# TreeRocketometer.net
KiCad netlist of a schematic drawn in EAGLE
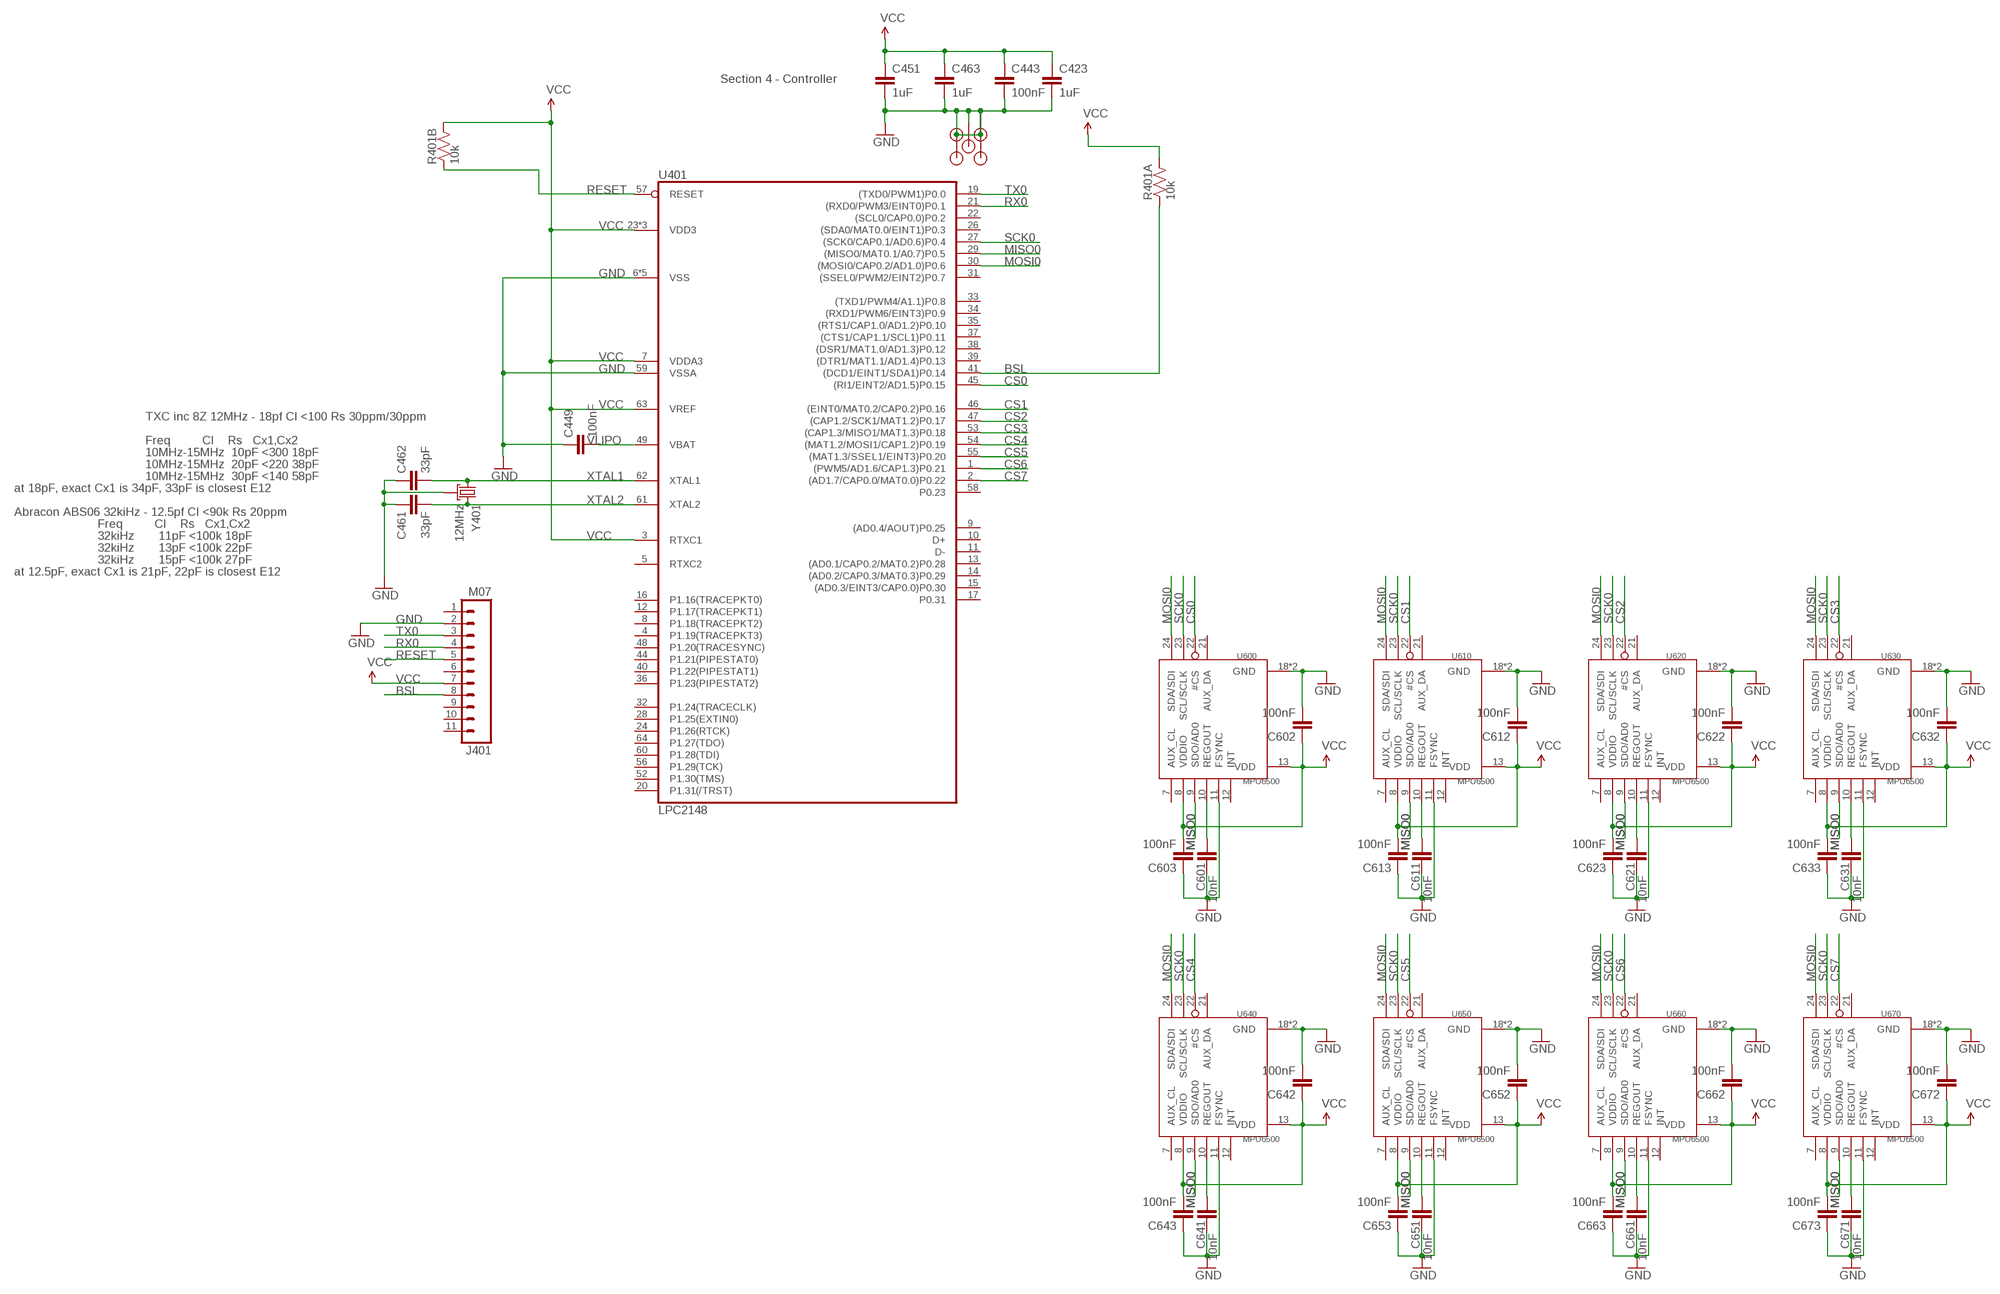
[diagram p0: schematic, sheet 1]

(export (version "E")
  (design (tool "Eeschema 10.0.6"))
  (components
    (comp (ref "C423")
      (value "1uF")
      (footprint "eagle-import:0402-CAP")
      (libsource (lib "eagle-import") (part "CAP0402-CAP"))
    )
    (comp (ref "C443")
      (value "100nF")
      (footprint "eagle-import:0402-CAP")
      (libsource (lib "eagle-import") (part "CAP0402-CAP"))
    )
    (comp (ref "C449")
      (value "100nF")
      (footprint "eagle-import:0402-CAP")
      (libsource (lib "eagle-import") (part "CAP0402-CAP"))
    )
    (comp (ref "C451")
      (value "1uF")
      (footprint "eagle-import:0402-CAP")
      (libsource (lib "eagle-import") (part "CAP0402-CAP"))
    )
    (comp (ref "C461")
      (value "33pF")
      (footprint "eagle-import:0402-CAP")
      (libsource (lib "eagle-import") (part "CAP0402-CAP"))
    )
    (comp (ref "C462")
      (value "33pF")
      (footprint "eagle-import:0402-CAP")
      (libsource (lib "eagle-import") (part "CAP0402-CAP"))
    )
    (comp (ref "C463")
      (value "1uF")
      (footprint "eagle-import:0402-CAP")
      (libsource (lib "eagle-import") (part "CAP0402-CAP"))
    )
    (comp (ref "C601")
      (value "10nF")
      (footprint "eagle-import:0402-CAP")
      (libsource (lib "eagle-import") (part "CAP0402-CAP"))
    )
    (comp (ref "C602")
      (value "100nF")
      (footprint "eagle-import:0402-CAP")
      (libsource (lib "eagle-import") (part "CAP0402-CAP"))
    )
    (comp (ref "C603")
      (value "100nF")
      (footprint "eagle-import:0402-CAP")
      (libsource (lib "eagle-import") (part "CAP0402-CAP"))
    )
    (comp (ref "C611")
      (value "10nF")
      (footprint "eagle-import:0402-CAP")
      (libsource (lib "eagle-import") (part "CAP0402-CAP"))
    )
    (comp (ref "C612")
      (value "100nF")
      (footprint "eagle-import:0402-CAP")
      (libsource (lib "eagle-import") (part "CAP0402-CAP"))
    )
    (comp (ref "C613")
      (value "100nF")
      (footprint "eagle-import:0402-CAP")
      (libsource (lib "eagle-import") (part "CAP0402-CAP"))
    )
    (comp (ref "C621")
      (value "10nF")
      (footprint "eagle-import:0402-CAP")
      (libsource (lib "eagle-import") (part "CAP0402-CAP"))
    )
    (comp (ref "C622")
      (value "100nF")
      (footprint "eagle-import:0402-CAP")
      (libsource (lib "eagle-import") (part "CAP0402-CAP"))
    )
    (comp (ref "C623")
      (value "100nF")
      (footprint "eagle-import:0402-CAP")
      (libsource (lib "eagle-import") (part "CAP0402-CAP"))
    )
    (comp (ref "C631")
      (value "10nF")
      (footprint "eagle-import:0402-CAP")
      (libsource (lib "eagle-import") (part "CAP0402-CAP"))
    )
    (comp (ref "C632")
      (value "100nF")
      (footprint "eagle-import:0402-CAP")
      (libsource (lib "eagle-import") (part "CAP0402-CAP"))
    )
    (comp (ref "C633")
      (value "100nF")
      (footprint "eagle-import:0402-CAP")
      (libsource (lib "eagle-import") (part "CAP0402-CAP"))
    )
    (comp (ref "C641")
      (value "10nF")
      (footprint "eagle-import:0402-CAP")
      (libsource (lib "eagle-import") (part "CAP0402-CAP"))
    )
    (comp (ref "C642")
      (value "100nF")
      (footprint "eagle-import:0402-CAP")
      (libsource (lib "eagle-import") (part "CAP0402-CAP"))
    )
    (comp (ref "C643")
      (value "100nF")
      (footprint "eagle-import:0402-CAP")
      (libsource (lib "eagle-import") (part "CAP0402-CAP"))
    )
    (comp (ref "C651")
      (value "10nF")
      (footprint "eagle-import:0402-CAP")
      (libsource (lib "eagle-import") (part "CAP0402-CAP"))
    )
    (comp (ref "C652")
      (value "100nF")
      (footprint "eagle-import:0402-CAP")
      (libsource (lib "eagle-import") (part "CAP0402-CAP"))
    )
    (comp (ref "C653")
      (value "100nF")
      (footprint "eagle-import:0402-CAP")
      (libsource (lib "eagle-import") (part "CAP0402-CAP"))
    )
    (comp (ref "C661")
      (value "10nF")
      (footprint "eagle-import:0402-CAP")
      (libsource (lib "eagle-import") (part "CAP0402-CAP"))
    )
    (comp (ref "C662")
      (value "100nF")
      (footprint "eagle-import:0402-CAP")
      (libsource (lib "eagle-import") (part "CAP0402-CAP"))
    )
    (comp (ref "C663")
      (value "100nF")
      (footprint "eagle-import:0402-CAP")
      (libsource (lib "eagle-import") (part "CAP0402-CAP"))
    )
    (comp (ref "C671")
      (value "10nF")
      (footprint "eagle-import:0402-CAP")
      (libsource (lib "eagle-import") (part "CAP0402-CAP"))
    )
    (comp (ref "C672")
      (value "100nF")
      (footprint "eagle-import:0402-CAP")
      (libsource (lib "eagle-import") (part "CAP0402-CAP"))
    )
    (comp (ref "C673")
      (value "100nF")
      (footprint "eagle-import:0402-CAP")
      (libsource (lib "eagle-import") (part "CAP0402-CAP"))
    )
    (comp (ref "J401")
      (value "M07")
      (footprint "eagle-import:1X11")
      (libsource (lib "eagle-import") (part "M11PTH"))
    )
    (comp (ref "JP1")
      (value "STANDOFF")
      (footprint "eagle-import:STANDOFF")
      (libsource (lib "eagle-import") (part "STANDOFF"))
    )
    (comp (ref "JP2")
      (value "STANDOFF")
      (footprint "eagle-import:STANDOFF")
      (libsource (lib "eagle-import") (part "STANDOFF"))
    )
    (comp (ref "JP3")
      (value "STANDOFF")
      (footprint "eagle-import:STANDOFF")
      (libsource (lib "eagle-import") (part "STANDOFF"))
    )
    (comp (ref "JP4")
      (value "STANDOFF")
      (footprint "eagle-import:STANDOFF")
      (libsource (lib "eagle-import") (part "STANDOFF"))
    )
    (comp (ref "JP5")
      (value "STANDOFF")
      (footprint "eagle-import:STANDOFF")
      (libsource (lib "eagle-import") (part "STANDOFF"))
    )
    (comp (ref "R401")
      (value "10k")
      (footprint "eagle-import:CRA04")
      (fields (field (name "DIGIKEY") "CRA4S810KCT-ND"))
      (libsource (lib "eagle-import") (part "RP404"))
    )
    (comp (ref "U401")
      (value "LPC2148")
      (footprint "eagle-import:LQFP64")
      (libsource (lib "eagle-import") (part "LPC2148"))
    )
    (comp (ref "U600")
      (value "MPU6500")
      (footprint "eagle-import:QFN24")
      (libsource (lib "eagle-import") (part "MPU6500"))
    )
    (comp (ref "U610")
      (value "MPU6500")
      (footprint "eagle-import:QFN24")
      (libsource (lib "eagle-import") (part "MPU6500"))
    )
    (comp (ref "U620")
      (value "MPU6500")
      (footprint "eagle-import:QFN24")
      (libsource (lib "eagle-import") (part "MPU6500"))
    )
    (comp (ref "U630")
      (value "MPU6500")
      (footprint "eagle-import:QFN24")
      (libsource (lib "eagle-import") (part "MPU6500"))
    )
    (comp (ref "U640")
      (value "MPU6500")
      (footprint "eagle-import:QFN24")
      (libsource (lib "eagle-import") (part "MPU6500"))
    )
    (comp (ref "U650")
      (value "MPU6500")
      (footprint "eagle-import:QFN24")
      (libsource (lib "eagle-import") (part "MPU6500"))
    )
    (comp (ref "U660")
      (value "MPU6500")
      (footprint "eagle-import:QFN24")
      (libsource (lib "eagle-import") (part "MPU6500"))
    )
    (comp (ref "U670")
      (value "MPU6500")
      (footprint "eagle-import:QFN24")
      (libsource (lib "eagle-import") (part "MPU6500"))
    )
    (comp (ref "Y401")
      (value "12MHz")
      (footprint "eagle-import:CRYSTAL_SMD_2MM_2_5MM")
      (libsource (lib "eagle-import") (part "CX2520"))
    )
  )
  (nets
    (net (code "1") (name "/BSL") (class "Default")
      (node (ref "J401") (pin "8") (pinfunction "8_8") (pintype "passive"))
      (node (ref "R401") (pin "1") (pinfunction "1_1") (pintype "passive"))
      (node (ref "U401") (pin "41") (pinfunction "(DCD1/EINT1/SDA1)P0.14_41") (pintype "bidirectional"))
    )
    (net (code "2") (name "/CS0") (class "Default")
      (node (ref "U401") (pin "45") (pinfunction "(RI1/EINT2/AD1.5)P0.15_45") (pintype "bidirectional"))
      (node (ref "U600") (pin "22") (pinfunction "#CS_22") (pintype "bidirectional"))
    )
    (net (code "3") (name "/CS1") (class "Default")
      (node (ref "U401") (pin "46") (pinfunction "(EINT0/MAT0.2/CAP0.2)P0.16_46") (pintype "bidirectional"))
      (node (ref "U610") (pin "22") (pinfunction "#CS_22") (pintype "bidirectional"))
    )
    (net (code "4") (name "/CS2") (class "Default")
      (node (ref "U401") (pin "47") (pinfunction "(CAP1.2/SCK1/MAT1.2)P0.17_47") (pintype "bidirectional"))
      (node (ref "U620") (pin "22") (pinfunction "#CS_22") (pintype "bidirectional"))
    )
    (net (code "5") (name "/CS3") (class "Default")
      (node (ref "U401") (pin "53") (pinfunction "(CAP1.3/MISO1/MAT1.3)P0.18_53") (pintype "bidirectional"))
      (node (ref "U630") (pin "22") (pinfunction "#CS_22") (pintype "bidirectional"))
    )
    (net (code "6") (name "/CS4") (class "Default")
      (node (ref "U401") (pin "54") (pinfunction "(MAT1.2/MOSI1/CAP1.2)P0.19_54") (pintype "bidirectional"))
      (node (ref "U640") (pin "22") (pinfunction "#CS_22") (pintype "bidirectional"))
    )
    (net (code "7") (name "/CS5") (class "Default")
      (node (ref "U401") (pin "55") (pinfunction "(MAT1.3/SSEL1/EINT3)P0.20_55") (pintype "bidirectional"))
      (node (ref "U650") (pin "22") (pinfunction "#CS_22") (pintype "bidirectional"))
    )
    (net (code "8") (name "/CS6") (class "Default")
      (node (ref "U401") (pin "1") (pinfunction "(PWM5/AD1.6/CAP1.3)P0.21_1") (pintype "bidirectional"))
      (node (ref "U660") (pin "22") (pinfunction "#CS_22") (pintype "bidirectional"))
    )
    (net (code "9") (name "/CS7") (class "Default")
      (node (ref "U401") (pin "2") (pinfunction "(AD1.7/CAP0.0/MAT0.0)P0.22_2") (pintype "bidirectional"))
      (node (ref "U670") (pin "22") (pinfunction "#CS_22") (pintype "bidirectional"))
    )
    (net (code "10") (name "/MISO0") (class "Default")
      (node (ref "U401") (pin "29") (pinfunction "(MISO0/MAT0.1/A0.7)P0.5_29") (pintype "bidirectional"))
      (node (ref "U600") (pin "9") (pinfunction "SDO/AD0_9") (pintype "output"))
      (node (ref "U610") (pin "9") (pinfunction "SDO/AD0_9") (pintype "output"))
      (node (ref "U620") (pin "9") (pinfunction "SDO/AD0_9") (pintype "output"))
      (node (ref "U630") (pin "9") (pinfunction "SDO/AD0_9") (pintype "output"))
      (node (ref "U640") (pin "9") (pinfunction "SDO/AD0_9") (pintype "output"))
      (node (ref "U650") (pin "9") (pinfunction "SDO/AD0_9") (pintype "output"))
      (node (ref "U660") (pin "9") (pinfunction "SDO/AD0_9") (pintype "output"))
      (node (ref "U670") (pin "9") (pinfunction "SDO/AD0_9") (pintype "output"))
    )
    (net (code "11") (name "/MOSI0") (class "Default")
      (node (ref "U401") (pin "30") (pinfunction "(MOSI0/CAP0.2/AD1.0)P0.6_30") (pintype "bidirectional"))
      (node (ref "U600") (pin "24") (pinfunction "SDA/SDI_24") (pintype "bidirectional"))
      (node (ref "U610") (pin "24") (pinfunction "SDA/SDI_24") (pintype "bidirectional"))
      (node (ref "U620") (pin "24") (pinfunction "SDA/SDI_24") (pintype "bidirectional"))
      (node (ref "U630") (pin "24") (pinfunction "SDA/SDI_24") (pintype "bidirectional"))
      (node (ref "U640") (pin "24") (pinfunction "SDA/SDI_24") (pintype "bidirectional"))
      (node (ref "U650") (pin "24") (pinfunction "SDA/SDI_24") (pintype "bidirectional"))
      (node (ref "U660") (pin "24") (pinfunction "SDA/SDI_24") (pintype "bidirectional"))
      (node (ref "U670") (pin "24") (pinfunction "SDA/SDI_24") (pintype "bidirectional"))
    )
    (net (code "12") (name "/RESET") (class "Default")
      (node (ref "J401") (pin "5") (pinfunction "5_5") (pintype "passive"))
      (node (ref "R401") (pin "2") (pinfunction "1_2") (pintype "passive"))
      (node (ref "U401") (pin "57") (pinfunction "RESET_57") (pintype "input"))
    )
    (net (code "13") (name "/RX0") (class "Default")
      (node (ref "J401") (pin "4") (pinfunction "4_4") (pintype "passive"))
      (node (ref "U401") (pin "21") (pinfunction "(RXD0/PWM3/EINT0)P0.1_21") (pintype "bidirectional"))
    )
    (net (code "14") (name "/SCK0") (class "Default")
      (node (ref "U401") (pin "27") (pinfunction "(SCK0/CAP0.1/AD0.6)P0.4_27") (pintype "bidirectional"))
      (node (ref "U600") (pin "23") (pinfunction "SCL/SCLK_23") (pintype "bidirectional"))
      (node (ref "U610") (pin "23") (pinfunction "SCL/SCLK_23") (pintype "bidirectional"))
      (node (ref "U620") (pin "23") (pinfunction "SCL/SCLK_23") (pintype "bidirectional"))
      (node (ref "U630") (pin "23") (pinfunction "SCL/SCLK_23") (pintype "bidirectional"))
      (node (ref "U640") (pin "23") (pinfunction "SCL/SCLK_23") (pintype "bidirectional"))
      (node (ref "U650") (pin "23") (pinfunction "SCL/SCLK_23") (pintype "bidirectional"))
      (node (ref "U660") (pin "23") (pinfunction "SCL/SCLK_23") (pintype "bidirectional"))
      (node (ref "U670") (pin "23") (pinfunction "SCL/SCLK_23") (pintype "bidirectional"))
    )
    (net (code "15") (name "/TX0") (class "Default")
      (node (ref "J401") (pin "3") (pinfunction "3_3") (pintype "passive"))
      (node (ref "U401") (pin "19") (pinfunction "(TXD0/PWM1)P0.0_19") (pintype "bidirectional"))
    )
    (net (code "16") (name "/VLIPO") (class "Default")
      (node (ref "C449") (pin "2") (pinfunction "2_2") (pintype "passive"))
      (node (ref "U401") (pin "49") (pinfunction "VBAT_49") (pintype "power_in"))
    )
    (net (code "17") (name "/XTAL1") (class "Default")
      (node (ref "C462") (pin "2") (pinfunction "2_2") (pintype "passive"))
      (node (ref "U401") (pin "62") (pinfunction "XTAL1_62") (pintype "input"))
      (node (ref "Y401") (pin "1") (pinfunction "1_1") (pintype "passive"))
    )
    (net (code "18") (name "/XTAL2") (class "Default")
      (node (ref "C461") (pin "2") (pinfunction "2_2") (pintype "passive"))
      (node (ref "U401") (pin "61") (pinfunction "XTAL2_61") (pintype "output"))
      (node (ref "Y401") (pin "3") (pinfunction "2_3") (pintype "passive"))
    )
    (net (code "19") (name "GND") (class "Default")
      (node (ref "C423") (pin "2") (pinfunction "2_2") (pintype "passive"))
      (node (ref "C443") (pin "2") (pinfunction "2_2") (pintype "passive"))
      (node (ref "C449") (pin "1") (pinfunction "1_1") (pintype "passive"))
      (node (ref "C451") (pin "2") (pinfunction "2_2") (pintype "passive"))
      (node (ref "C461") (pin "1") (pinfunction "1_1") (pintype "passive"))
      (node (ref "C462") (pin "1") (pinfunction "1_1") (pintype "passive"))
      (node (ref "C463") (pin "2") (pinfunction "2_2") (pintype "passive"))
      (node (ref "C601") (pin "2") (pinfunction "2_2") (pintype "passive"))
      (node (ref "C602") (pin "2") (pinfunction "2_2") (pintype "passive"))
      (node (ref "C603") (pin "1") (pinfunction "1_1") (pintype "passive"))
      (node (ref "C611") (pin "2") (pinfunction "2_2") (pintype "passive"))
      (node (ref "C612") (pin "2") (pinfunction "2_2") (pintype "passive"))
      (node (ref "C613") (pin "1") (pinfunction "1_1") (pintype "passive"))
      (node (ref "C621") (pin "2") (pinfunction "2_2") (pintype "passive"))
      (node (ref "C622") (pin "2") (pinfunction "2_2") (pintype "passive"))
      (node (ref "C623") (pin "1") (pinfunction "1_1") (pintype "passive"))
      (node (ref "C631") (pin "2") (pinfunction "2_2") (pintype "passive"))
      (node (ref "C632") (pin "2") (pinfunction "2_2") (pintype "passive"))
      (node (ref "C633") (pin "1") (pinfunction "1_1") (pintype "passive"))
      (node (ref "C641") (pin "2") (pinfunction "2_2") (pintype "passive"))
      (node (ref "C642") (pin "2") (pinfunction "2_2") (pintype "passive"))
      (node (ref "C643") (pin "1") (pinfunction "1_1") (pintype "passive"))
      (node (ref "C651") (pin "2") (pinfunction "2_2") (pintype "passive"))
      (node (ref "C652") (pin "2") (pinfunction "2_2") (pintype "passive"))
      (node (ref "C653") (pin "1") (pinfunction "1_1") (pintype "passive"))
      (node (ref "C661") (pin "2") (pinfunction "2_2") (pintype "passive"))
      (node (ref "C662") (pin "2") (pinfunction "2_2") (pintype "passive"))
      (node (ref "C663") (pin "1") (pinfunction "1_1") (pintype "passive"))
      (node (ref "C671") (pin "2") (pinfunction "2_2") (pintype "passive"))
      (node (ref "C672") (pin "2") (pinfunction "2_2") (pintype "passive"))
      (node (ref "C673") (pin "1") (pinfunction "1_1") (pintype "passive"))
      (node (ref "J401") (pin "2") (pinfunction "2_2") (pintype "passive"))
      (node (ref "JP1") (pin "P$1") (pinfunction "P$1_P$1") (pintype "bidirectional"))
      (node (ref "JP2") (pin "P$1") (pinfunction "P$1_P$1") (pintype "bidirectional"))
      (node (ref "JP3") (pin "P$1") (pinfunction "P$1_P$1") (pintype "bidirectional"))
      (node (ref "JP4") (pin "P$1") (pinfunction "P$1_P$1") (pintype "bidirectional"))
      (node (ref "JP5") (pin "P$1") (pinfunction "P$1_P$1") (pintype "bidirectional"))
      (node (ref "U401") (pin "18") (pinfunction "VSS_18") (pintype "power_in"))
      (node (ref "U401") (pin "25") (pinfunction "VSS_25") (pintype "power_in"))
      (node (ref "U401") (pin "42") (pinfunction "VSS_42") (pintype "power_in"))
      (node (ref "U401") (pin "50") (pinfunction "VSS_50") (pintype "power_in"))
      (node (ref "U401") (pin "59") (pinfunction "VSSA_59") (pintype "power_in"))
      (node (ref "U401") (pin "6") (pinfunction "VSS_6") (pintype "power_in"))
      (node (ref "U600") (pin "11") (pinfunction "FSYNC_11") (pintype "bidirectional"))
      (node (ref "U600") (pin "18") (pinfunction "GND_18") (pintype "power_in"))
      (node (ref "U600") (pin "20") (pinfunction "GND_20") (pintype "power_in"))
      (node (ref "U610") (pin "11") (pinfunction "FSYNC_11") (pintype "bidirectional"))
      (node (ref "U610") (pin "18") (pinfunction "GND_18") (pintype "power_in"))
      (node (ref "U610") (pin "20") (pinfunction "GND_20") (pintype "power_in"))
      (node (ref "U620") (pin "11") (pinfunction "FSYNC_11") (pintype "bidirectional"))
      (node (ref "U620") (pin "18") (pinfunction "GND_18") (pintype "power_in"))
      (node (ref "U620") (pin "20") (pinfunction "GND_20") (pintype "power_in"))
      (node (ref "U630") (pin "11") (pinfunction "FSYNC_11") (pintype "bidirectional"))
      (node (ref "U630") (pin "18") (pinfunction "GND_18") (pintype "power_in"))
      (node (ref "U630") (pin "20") (pinfunction "GND_20") (pintype "power_in"))
      (node (ref "U640") (pin "11") (pinfunction "FSYNC_11") (pintype "bidirectional"))
      (node (ref "U640") (pin "18") (pinfunction "GND_18") (pintype "power_in"))
      (node (ref "U640") (pin "20") (pinfunction "GND_20") (pintype "power_in"))
      (node (ref "U650") (pin "11") (pinfunction "FSYNC_11") (pintype "bidirectional"))
      (node (ref "U650") (pin "18") (pinfunction "GND_18") (pintype "power_in"))
      (node (ref "U650") (pin "20") (pinfunction "GND_20") (pintype "power_in"))
      (node (ref "U660") (pin "11") (pinfunction "FSYNC_11") (pintype "bidirectional"))
      (node (ref "U660") (pin "18") (pinfunction "GND_18") (pintype "power_in"))
      (node (ref "U660") (pin "20") (pinfunction "GND_20") (pintype "power_in"))
      (node (ref "U670") (pin "11") (pinfunction "FSYNC_11") (pintype "bidirectional"))
      (node (ref "U670") (pin "18") (pinfunction "GND_18") (pintype "power_in"))
      (node (ref "U670") (pin "20") (pinfunction "GND_20") (pintype "power_in"))
      (node (ref "Y401") (pin "2") (pinfunction "GND_2") (pintype "passive"))
      (node (ref "Y401") (pin "4") (pinfunction "GND_4") (pintype "passive"))
    )
    (net (code "20") (name "Net-(U600-REGOUT)") (class "Default")
      (node (ref "C601") (pin "1") (pinfunction "1_1") (pintype "passive"))
      (node (ref "U600") (pin "10") (pinfunction "REGOUT_10") (pintype "bidirectional"))
    )
    (net (code "21") (name "Net-(U610-REGOUT)") (class "Default")
      (node (ref "C611") (pin "1") (pinfunction "1_1") (pintype "passive"))
      (node (ref "U610") (pin "10") (pinfunction "REGOUT_10") (pintype "bidirectional"))
    )
    (net (code "22") (name "Net-(U620-REGOUT)") (class "Default")
      (node (ref "C621") (pin "1") (pinfunction "1_1") (pintype "passive"))
      (node (ref "U620") (pin "10") (pinfunction "REGOUT_10") (pintype "bidirectional"))
    )
    (net (code "23") (name "Net-(U630-REGOUT)") (class "Default")
      (node (ref "C631") (pin "1") (pinfunction "1_1") (pintype "passive"))
      (node (ref "U630") (pin "10") (pinfunction "REGOUT_10") (pintype "bidirectional"))
    )
    (net (code "24") (name "Net-(U640-REGOUT)") (class "Default")
      (node (ref "C641") (pin "1") (pinfunction "1_1") (pintype "passive"))
      (node (ref "U640") (pin "10") (pinfunction "REGOUT_10") (pintype "bidirectional"))
    )
    (net (code "25") (name "Net-(U650-REGOUT)") (class "Default")
      (node (ref "C651") (pin "1") (pinfunction "1_1") (pintype "passive"))
      (node (ref "U650") (pin "10") (pinfunction "REGOUT_10") (pintype "bidirectional"))
    )
    (net (code "26") (name "Net-(U660-REGOUT)") (class "Default")
      (node (ref "C661") (pin "1") (pinfunction "1_1") (pintype "passive"))
      (node (ref "U660") (pin "10") (pinfunction "REGOUT_10") (pintype "bidirectional"))
    )
    (net (code "27") (name "Net-(U670-REGOUT)") (class "Default")
      (node (ref "C671") (pin "1") (pinfunction "1_1") (pintype "passive"))
      (node (ref "U670") (pin "10") (pinfunction "REGOUT_10") (pintype "bidirectional"))
    )
    (net (code "28") (name "VCC") (class "Default")
      (node (ref "C423") (pin "1") (pinfunction "1_1") (pintype "passive"))
      (node (ref "C443") (pin "1") (pinfunction "1_1") (pintype "passive"))
      (node (ref "C451") (pin "1") (pinfunction "1_1") (pintype "passive"))
      (node (ref "C463") (pin "1") (pinfunction "1_1") (pintype "passive"))
      (node (ref "C602") (pin "1") (pinfunction "1_1") (pintype "passive"))
      (node (ref "C603") (pin "2") (pinfunction "2_2") (pintype "passive"))
      (node (ref "C612") (pin "1") (pinfunction "1_1") (pintype "passive"))
      (node (ref "C613") (pin "2") (pinfunction "2_2") (pintype "passive"))
      (node (ref "C622") (pin "1") (pinfunction "1_1") (pintype "passive"))
      (node (ref "C623") (pin "2") (pinfunction "2_2") (pintype "passive"))
      (node (ref "C632") (pin "1") (pinfunction "1_1") (pintype "passive"))
      (node (ref "C633") (pin "2") (pinfunction "2_2") (pintype "passive"))
      (node (ref "C642") (pin "1") (pinfunction "1_1") (pintype "passive"))
      (node (ref "C643") (pin "2") (pinfunction "2_2") (pintype "passive"))
      (node (ref "C652") (pin "1") (pinfunction "1_1") (pintype "passive"))
      (node (ref "C653") (pin "2") (pinfunction "2_2") (pintype "passive"))
      (node (ref "C662") (pin "1") (pinfunction "1_1") (pintype "passive"))
      (node (ref "C663") (pin "2") (pinfunction "2_2") (pintype "passive"))
      (node (ref "C672") (pin "1") (pinfunction "1_1") (pintype "passive"))
      (node (ref "C673") (pin "2") (pinfunction "2_2") (pintype "passive"))
      (node (ref "J401") (pin "7") (pinfunction "7_7") (pintype "passive"))
      (node (ref "R401") (pin "7") (pinfunction "2_7") (pintype "passive"))
      (node (ref "R401") (pin "8") (pinfunction "2_8") (pintype "passive"))
      (node (ref "U401") (pin "23") (pinfunction "VDD3_23") (pintype "power_in"))
      (node (ref "U401") (pin "3") (pinfunction "RTXC1_3") (pintype "input"))
      (node (ref "U401") (pin "43") (pinfunction "VDD3_43") (pintype "power_in"))
      (node (ref "U401") (pin "51") (pinfunction "VDD3_51") (pintype "power_in"))
      (node (ref "U401") (pin "63") (pinfunction "VREF_63") (pintype "input"))
      (node (ref "U401") (pin "7") (pinfunction "VDDA3_7") (pintype "power_in"))
      (node (ref "U600") (pin "13") (pinfunction "VDD_13") (pintype "power_in"))
      (node (ref "U600") (pin "8") (pinfunction "VDDIO_8") (pintype "bidirectional"))
      (node (ref "U610") (pin "13") (pinfunction "VDD_13") (pintype "power_in"))
      (node (ref "U610") (pin "8") (pinfunction "VDDIO_8") (pintype "bidirectional"))
      (node (ref "U620") (pin "13") (pinfunction "VDD_13") (pintype "power_in"))
      (node (ref "U620") (pin "8") (pinfunction "VDDIO_8") (pintype "bidirectional"))
      (node (ref "U630") (pin "13") (pinfunction "VDD_13") (pintype "power_in"))
      (node (ref "U630") (pin "8") (pinfunction "VDDIO_8") (pintype "bidirectional"))
      (node (ref "U640") (pin "13") (pinfunction "VDD_13") (pintype "power_in"))
      (node (ref "U640") (pin "8") (pinfunction "VDDIO_8") (pintype "bidirectional"))
      (node (ref "U650") (pin "13") (pinfunction "VDD_13") (pintype "power_in"))
      (node (ref "U650") (pin "8") (pinfunction "VDDIO_8") (pintype "bidirectional"))
      (node (ref "U660") (pin "13") (pinfunction "VDD_13") (pintype "power_in"))
      (node (ref "U660") (pin "8") (pinfunction "VDDIO_8") (pintype "bidirectional"))
      (node (ref "U670") (pin "13") (pinfunction "VDD_13") (pintype "power_in"))
      (node (ref "U670") (pin "8") (pinfunction "VDDIO_8") (pintype "bidirectional"))
    )
    (net (code "29") (name "unconnected-(J401-Pad1)") (class "Default")
      (node (ref "J401") (pin "1") (pinfunction "1_1") (pintype "passive"))
    )
    (net (code "30") (name "unconnected-(J401-Pad6)") (class "Default")
      (node (ref "J401") (pin "6") (pinfunction "6_6") (pintype "passive"))
    )
    (net (code "31") (name "unconnected-(J401-Pad9)") (class "Default")
      (node (ref "J401") (pin "9") (pinfunction "9_9") (pintype "passive"))
    )
    (net (code "32") (name "unconnected-(J401-Pad10)") (class "Default")
      (node (ref "J401") (pin "10") (pinfunction "10_10") (pintype "passive"))
    )
    (net (code "33") (name "unconnected-(J401-Pad11)") (class "Default")
      (node (ref "J401") (pin "11") (pinfunction "11_11") (pintype "passive"))
    )
    (net (code "34") (name "unconnected-(U401-(AD0.1{slash}CAP0.2{slash}MAT0.2)P0.28-Pad13)") (class "Default")
      (node (ref "U401") (pin "13") (pinfunction "(AD0.1/CAP0.2/MAT0.2)P0.28_13") (pintype "bidirectional"))
    )
    (net (code "35") (name "unconnected-(U401-(AD0.2{slash}CAP0.3{slash}MAT0.3)P0.29-Pad14)") (class "Default")
      (node (ref "U401") (pin "14") (pinfunction "(AD0.2/CAP0.3/MAT0.3)P0.29_14") (pintype "bidirectional"))
    )
    (net (code "36") (name "unconnected-(U401-(AD0.3{slash}EINT3{slash}CAP0.0)P0.30-Pad15)") (class "Default")
      (node (ref "U401") (pin "15") (pinfunction "(AD0.3/EINT3/CAP0.0)P0.30_15") (pintype "bidirectional"))
    )
    (net (code "37") (name "unconnected-(U401-(AD0.4{slash}AOUT)P0.25-Pad9)") (class "Default")
      (node (ref "U401") (pin "9") (pinfunction "(AD0.4/AOUT)P0.25_9") (pintype "bidirectional"))
    )
    (net (code "38") (name "unconnected-(U401-(CTS1{slash}CAP1.1{slash}SCL1)P0.11-Pad37)") (class "Default")
      (node (ref "U401") (pin "37") (pinfunction "(CTS1/CAP1.1/SCL1)P0.11_37") (pintype "bidirectional"))
    )
    (net (code "39") (name "unconnected-(U401-(DSR1{slash}MAT1.0{slash}AD1.3)P0.12-Pad38)") (class "Default")
      (node (ref "U401") (pin "38") (pinfunction "(DSR1/MAT1.0/AD1.3)P0.12_38") (pintype "bidirectional"))
    )
    (net (code "40") (name "unconnected-(U401-(DTR1{slash}MAT1.1{slash}AD1.4)P0.13-Pad39)") (class "Default")
      (node (ref "U401") (pin "39") (pinfunction "(DTR1/MAT1.1/AD1.4)P0.13_39") (pintype "bidirectional"))
    )
    (net (code "41") (name "unconnected-(U401-(RTS1{slash}CAP1.0{slash}AD1.2)P0.10-Pad35)") (class "Default")
      (node (ref "U401") (pin "35") (pinfunction "(RTS1/CAP1.0/AD1.2)P0.10_35") (pintype "bidirectional"))
    )
    (net (code "42") (name "unconnected-(U401-(RXD1{slash}PWM6{slash}EINT3)P0.9-Pad34)") (class "Default")
      (node (ref "U401") (pin "34") (pinfunction "(RXD1/PWM6/EINT3)P0.9_34") (pintype "bidirectional"))
    )
    (net (code "43") (name "unconnected-(U401-(SCL0{slash}CAP0.0)P0.2-Pad22)") (class "Default")
      (node (ref "U401") (pin "22") (pinfunction "(SCL0/CAP0.0)P0.2_22") (pintype "bidirectional"))
    )
    (net (code "44") (name "unconnected-(U401-(SDA0{slash}MAT0.0{slash}EINT1)P0.3-Pad26)") (class "Default")
      (node (ref "U401") (pin "26") (pinfunction "(SDA0/MAT0.0/EINT1)P0.3_26") (pintype "bidirectional"))
    )
    (net (code "45") (name "unconnected-(U401-(SSEL0{slash}PWM2{slash}EINT2)P0.7-Pad31)") (class "Default")
      (node (ref "U401") (pin "31") (pinfunction "(SSEL0/PWM2/EINT2)P0.7_31") (pintype "bidirectional"))
    )
    (net (code "46") (name "unconnected-(U401-(TXD1{slash}PWM4{slash}A1.1)P0.8-Pad33)") (class "Default")
      (node (ref "U401") (pin "33") (pinfunction "(TXD1/PWM4/A1.1)P0.8_33") (pintype "bidirectional"))
    )
    (net (code "47") (name "unconnected-(U401-D+-Pad10)") (class "Default")
      (node (ref "U401") (pin "10") (pinfunction "D+_10") (pintype "bidirectional"))
    )
    (net (code "48") (name "unconnected-(U401-D--Pad11)") (class "Default")
      (node (ref "U401") (pin "11") (pinfunction "D-_11") (pintype "bidirectional"))
    )
    (net (code "49") (name "unconnected-(U401-P0.23-Pad58)") (class "Default")
      (node (ref "U401") (pin "58") (pinfunction "P0.23_58") (pintype "bidirectional"))
    )
    (net (code "50") (name "unconnected-(U401-P0.31-Pad17)") (class "Default")
      (node (ref "U401") (pin "17") (pinfunction "P0.31_17") (pintype "output"))
    )
    (net (code "51") (name "unconnected-(U401-P1.16(TRACEPKT0)-Pad16)") (class "Default")
      (node (ref "U401") (pin "16") (pinfunction "P1.16(TRACEPKT0)_16") (pintype "bidirectional"))
    )
    (net (code "52") (name "unconnected-(U401-P1.17(TRACEPKT1)-Pad12)") (class "Default")
      (node (ref "U401") (pin "12") (pinfunction "P1.17(TRACEPKT1)_12") (pintype "bidirectional"))
    )
    (net (code "53") (name "unconnected-(U401-P1.18(TRACEPKT2)-Pad8)") (class "Default")
      (node (ref "U401") (pin "8") (pinfunction "P1.18(TRACEPKT2)_8") (pintype "bidirectional"))
    )
    (net (code "54") (name "unconnected-(U401-P1.19(TRACEPKT3)-Pad4)") (class "Default")
      (node (ref "U401") (pin "4") (pinfunction "P1.19(TRACEPKT3)_4") (pintype "bidirectional"))
    )
    (net (code "55") (name "unconnected-(U401-P1.20(TRACESYNC)-Pad48)") (class "Default")
      (node (ref "U401") (pin "48") (pinfunction "P1.20(TRACESYNC)_48") (pintype "bidirectional"))
    )
    (net (code "56") (name "unconnected-(U401-P1.21(PIPESTAT0)-Pad44)") (class "Default")
      (node (ref "U401") (pin "44") (pinfunction "P1.21(PIPESTAT0)_44") (pintype "bidirectional"))
    )
    (net (code "57") (name "unconnected-(U401-P1.22(PIPESTAT1)-Pad40)") (class "Default")
      (node (ref "U401") (pin "40") (pinfunction "P1.22(PIPESTAT1)_40") (pintype "bidirectional"))
    )
    (net (code "58") (name "unconnected-(U401-P1.23(PIPESTAT2)-Pad36)") (class "Default")
      (node (ref "U401") (pin "36") (pinfunction "P1.23(PIPESTAT2)_36") (pintype "bidirectional"))
    )
    (net (code "59") (name "unconnected-(U401-P1.24(TRACECLK)-Pad32)") (class "Default")
      (node (ref "U401") (pin "32") (pinfunction "P1.24(TRACECLK)_32") (pintype "bidirectional"))
    )
    (net (code "60") (name "unconnected-(U401-P1.25(EXTIN0)-Pad28)") (class "Default")
      (node (ref "U401") (pin "28") (pinfunction "P1.25(EXTIN0)_28") (pintype "bidirectional"))
    )
    (net (code "61") (name "unconnected-(U401-P1.26(RTCK)-Pad24)") (class "Default")
      (node (ref "U401") (pin "24") (pinfunction "P1.26(RTCK)_24") (pintype "bidirectional"))
    )
    (net (code "62") (name "unconnected-(U401-P1.27(TDO)-Pad64)") (class "Default")
      (node (ref "U401") (pin "64") (pinfunction "P1.27(TDO)_64") (pintype "bidirectional"))
    )
    (net (code "63") (name "unconnected-(U401-P1.28(TDI)-Pad60)") (class "Default")
      (node (ref "U401") (pin "60") (pinfunction "P1.28(TDI)_60") (pintype "bidirectional"))
    )
    (net (code "64") (name "unconnected-(U401-P1.29(TCK)-Pad56)") (class "Default")
      (node (ref "U401") (pin "56") (pinfunction "P1.29(TCK)_56") (pintype "bidirectional"))
    )
    (net (code "65") (name "unconnected-(U401-P1.30(TMS)-Pad52)") (class "Default")
      (node (ref "U401") (pin "52") (pinfunction "P1.30(TMS)_52") (pintype "bidirectional"))
    )
    (net (code "66") (name "unconnected-(U401-P1.31({slash}TRST)-Pad20)") (class "Default")
      (node (ref "U401") (pin "20") (pinfunction "P1.31(/TRST)_20") (pintype "bidirectional"))
    )
    (net (code "67") (name "unconnected-(U401-RTXC2-Pad5)") (class "Default")
      (node (ref "U401") (pin "5") (pinfunction "RTXC2_5") (pintype "output"))
    )
    (net (code "68") (name "unconnected-(U600-AUX_CL-Pad7)") (class "Default")
      (node (ref "U600") (pin "7") (pinfunction "AUX_CL_7") (pintype "bidirectional"))
    )
    (net (code "69") (name "unconnected-(U600-AUX_DA-Pad21)") (class "Default")
      (node (ref "U600") (pin "21") (pinfunction "AUX_DA_21") (pintype "bidirectional"))
    )
    (net (code "70") (name "unconnected-(U600-INT-Pad12)") (class "Default")
      (node (ref "U600") (pin "12") (pinfunction "INT_12") (pintype "output"))
    )
    (net (code "71") (name "unconnected-(U610-AUX_CL-Pad7)") (class "Default")
      (node (ref "U610") (pin "7") (pinfunction "AUX_CL_7") (pintype "bidirectional"))
    )
    (net (code "72") (name "unconnected-(U610-AUX_DA-Pad21)") (class "Default")
      (node (ref "U610") (pin "21") (pinfunction "AUX_DA_21") (pintype "bidirectional"))
    )
    (net (code "73") (name "unconnected-(U610-INT-Pad12)") (class "Default")
      (node (ref "U610") (pin "12") (pinfunction "INT_12") (pintype "output"))
    )
    (net (code "74") (name "unconnected-(U620-AUX_CL-Pad7)") (class "Default")
      (node (ref "U620") (pin "7") (pinfunction "AUX_CL_7") (pintype "bidirectional"))
    )
    (net (code "75") (name "unconnected-(U620-AUX_DA-Pad21)") (class "Default")
      (node (ref "U620") (pin "21") (pinfunction "AUX_DA_21") (pintype "bidirectional"))
    )
    (net (code "76") (name "unconnected-(U620-INT-Pad12)") (class "Default")
      (node (ref "U620") (pin "12") (pinfunction "INT_12") (pintype "output"))
    )
    (net (code "77") (name "unconnected-(U630-AUX_CL-Pad7)") (class "Default")
      (node (ref "U630") (pin "7") (pinfunction "AUX_CL_7") (pintype "bidirectional"))
    )
    (net (code "78") (name "unconnected-(U630-AUX_DA-Pad21)") (class "Default")
      (node (ref "U630") (pin "21") (pinfunction "AUX_DA_21") (pintype "bidirectional"))
    )
    (net (code "79") (name "unconnected-(U630-INT-Pad12)") (class "Default")
      (node (ref "U630") (pin "12") (pinfunction "INT_12") (pintype "output"))
    )
    (net (code "80") (name "unconnected-(U640-AUX_CL-Pad7)") (class "Default")
      (node (ref "U640") (pin "7") (pinfunction "AUX_CL_7") (pintype "bidirectional"))
    )
    (net (code "81") (name "unconnected-(U640-AUX_DA-Pad21)") (class "Default")
      (node (ref "U640") (pin "21") (pinfunction "AUX_DA_21") (pintype "bidirectional"))
    )
    (net (code "82") (name "unconnected-(U640-INT-Pad12)") (class "Default")
      (node (ref "U640") (pin "12") (pinfunction "INT_12") (pintype "output"))
    )
    (net (code "83") (name "unconnected-(U650-AUX_CL-Pad7)") (class "Default")
      (node (ref "U650") (pin "7") (pinfunction "AUX_CL_7") (pintype "bidirectional"))
    )
    (net (code "84") (name "unconnected-(U650-AUX_DA-Pad21)") (class "Default")
      (node (ref "U650") (pin "21") (pinfunction "AUX_DA_21") (pintype "bidirectional"))
    )
    (net (code "85") (name "unconnected-(U650-INT-Pad12)") (class "Default")
      (node (ref "U650") (pin "12") (pinfunction "INT_12") (pintype "output"))
    )
    (net (code "86") (name "unconnected-(U660-AUX_CL-Pad7)") (class "Default")
      (node (ref "U660") (pin "7") (pinfunction "AUX_CL_7") (pintype "bidirectional"))
    )
    (net (code "87") (name "unconnected-(U660-AUX_DA-Pad21)") (class "Default")
      (node (ref "U660") (pin "21") (pinfunction "AUX_DA_21") (pintype "bidirectional"))
    )
    (net (code "88") (name "unconnected-(U660-INT-Pad12)") (class "Default")
      (node (ref "U660") (pin "12") (pinfunction "INT_12") (pintype "output"))
    )
    (net (code "89") (name "unconnected-(U670-AUX_CL-Pad7)") (class "Default")
      (node (ref "U670") (pin "7") (pinfunction "AUX_CL_7") (pintype "bidirectional"))
    )
    (net (code "90") (name "unconnected-(U670-AUX_DA-Pad21)") (class "Default")
      (node (ref "U670") (pin "21") (pinfunction "AUX_DA_21") (pintype "bidirectional"))
    )
    (net (code "91") (name "unconnected-(U670-INT-Pad12)") (class "Default")
      (node (ref "U670") (pin "12") (pinfunction "INT_12") (pintype "output"))
    )
  )
)
